# Amplifiers.net
KiCad netlist of a schematic drawn in Altium Designer
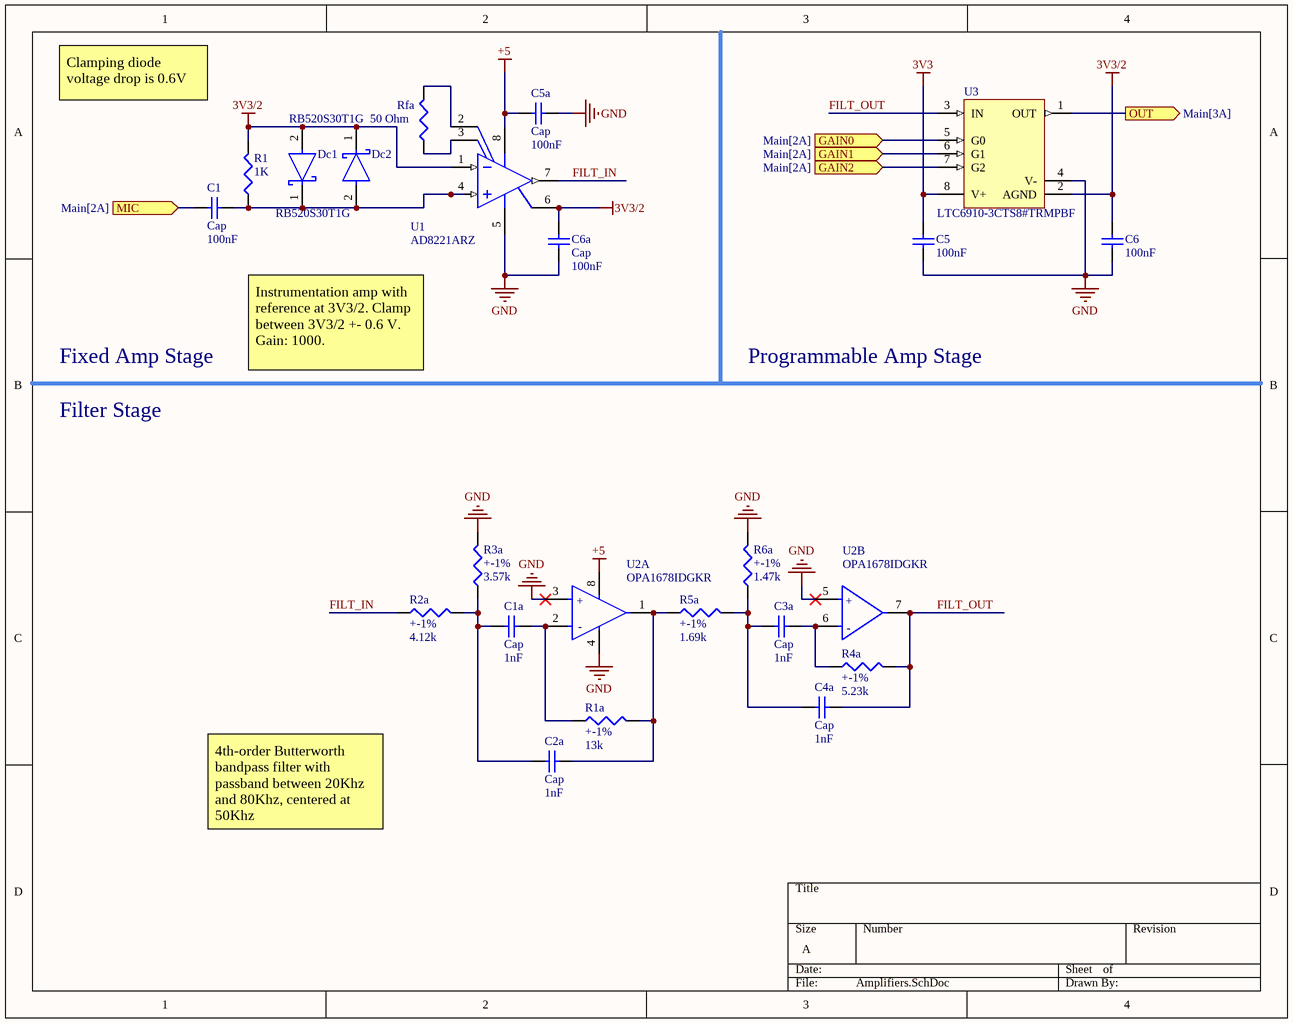
[diagram p0: Amplifiers.SchDoc]

(export (version "E")
  (design (tool "Eeschema 10.0.6"))
  (components
    (comp (ref "C1")
      (value "Cap")
      (footprint "C0805")
      (description "Capacitor")
      (fields (field (name "ALTIUM_VALUE") "100nF") (field (name "PUBLISHER") "Altium Limited"))
      (libsource (lib "Miscellaneous Devices") (part "Cap"))
    )
    (comp (ref "C1a")
      (value "Cap")
      (footprint "C0805")
      (description "Capacitor")
      (fields (field (name "ALTIUM_VALUE") "1nF") (field (name "PUBLISHER") "Altium Limited"))
      (libsource (lib "Miscellaneous Devices") (part "Cap"))
    )
    (comp (ref "C2a")
      (value "Cap")
      (footprint "C0805")
      (description "Capacitor")
      (fields (field (name "ALTIUM_VALUE") "1nF") (field (name "PUBLISHER") "Altium Limited"))
      (libsource (lib "Miscellaneous Devices") (part "Cap"))
    )
    (comp (ref "C3a")
      (value "Cap")
      (footprint "C0805")
      (description "Capacitor")
      (fields (field (name "ALTIUM_VALUE") "1nF") (field (name "PUBLISHER") "Altium Limited"))
      (libsource (lib "Miscellaneous Devices") (part "Cap"))
    )
    (comp (ref "C4a")
      (value "Cap")
      (footprint "C0805")
      (description "Capacitor")
      (fields (field (name "ALTIUM_VALUE") "1nF") (field (name "PUBLISHER") "Altium Limited"))
      (libsource (lib "Miscellaneous Devices") (part "Cap"))
    )
    (comp (ref "C5")
      (value "100nF")
      (footprint "C0805")
      (description "Capacitor")
      (fields (field (name "PUBLISHER") "Altium Limited"))
      (libsource (lib "Miscellaneous Devices") (part "Cap"))
    )
    (comp (ref "C5a")
      (value "Cap")
      (footprint "C0805")
      (description "Capacitor")
      (fields (field (name "ALTIUM_VALUE") "100nF") (field (name "PUBLISHER") "Altium Limited"))
      (libsource (lib "Miscellaneous Devices") (part "Cap"))
    )
    (comp (ref "C6")
      (value "100nF")
      (footprint "C0805")
      (description "Capacitor")
      (fields (field (name "PUBLISHER") "Altium Limited"))
      (libsource (lib "Miscellaneous Devices") (part "Cap"))
    )
    (comp (ref "C6a")
      (value "Cap")
      (footprint "C0805")
      (description "Capacitor")
      (fields (field (name "ALTIUM_VALUE") "100nF") (field (name "PUBLISHER") "Altium Limited"))
      (libsource (lib "Miscellaneous Devices") (part "Cap"))
    )
    (comp (ref "Dc1")
      (value "RB520S30T1G")
      (footprint "FP-502-01-MFG")
      (description "DIODE SCHOTTKY 30V 200MA SOD523")
      (libsource (lib "Altium Content Vault") (part "1d6ec82d83fb6aee721767c19dac4b9"))
    )
    (comp (ref "Dc2")
      (value "RB520S30T1G")
      (footprint "FP-502-01-MFG")
      (description "DIODE SCHOTTKY 30V 200MA SOD523")
      (libsource (lib "Altium Content Vault") (part "1d6ec82d83fb6aee721767c19dac4b9"))
    )
    (comp (ref "R1")
      (value "1K")
      (footprint "J1-0603")
      (description "Resistor")
      (fields (field (name "PUBLISHER") "Altium Limited"))
      (libsource (lib "Miscellaneous Devices") (part "Res3"))
    )
    (comp (ref "R1a")
      (value "+-1%")
      (footprint "J1-0603")
      (description "Resistor")
      (fields (field (name "ALTIUM_VALUE") "13k") (field (name "PUBLISHER") "Altium Limited"))
      (libsource (lib "Miscellaneous Devices") (part "Res3"))
    )
    (comp (ref "R2a")
      (value "+-1%")
      (footprint "J1-0603")
      (description "Resistor")
      (fields (field (name "ALTIUM_VALUE") "4.12k") (field (name "PUBLISHER") "Altium Limited"))
      (libsource (lib "Miscellaneous Devices") (part "Res3"))
    )
    (comp (ref "R3a")
      (value "+-1%")
      (footprint "J1-0603")
      (description "Resistor")
      (fields (field (name "ALTIUM_VALUE") "3.57k") (field (name "PUBLISHER") "Altium Limited"))
      (libsource (lib "Miscellaneous Devices") (part "Res3"))
    )
    (comp (ref "R4a")
      (value "+-1%")
      (footprint "J1-0603")
      (description "Resistor")
      (fields (field (name "ALTIUM_VALUE") "5.23k") (field (name "PUBLISHER") "Altium Limited"))
      (libsource (lib "Miscellaneous Devices") (part "Res3"))
    )
    (comp (ref "R5a")
      (value "+-1%")
      (footprint "J1-0603")
      (description "Resistor")
      (fields (field (name "ALTIUM_VALUE") "1.69k") (field (name "PUBLISHER") "Altium Limited"))
      (libsource (lib "Miscellaneous Devices") (part "Res3"))
    )
    (comp (ref "R6a")
      (value "+-1%")
      (footprint "J1-0603")
      (description "Resistor")
      (fields (field (name "ALTIUM_VALUE") "1.47k") (field (name "PUBLISHER") "Altium Limited"))
      (libsource (lib "Miscellaneous Devices") (part "Res3"))
    )
    (comp (ref "Rfa")
      (value "50 Ohm")
      (footprint "J1-0603")
      (description "Resistor")
      (fields (field (name "PUBLISHER") "Altium Limited"))
      (libsource (lib "Miscellaneous Devices") (part "Res3"))
    )
    (comp (ref "U1")
      (value "AD8221ARZ")
      (footprint "ADI-R-8_M")
      (description "Precision Instrumentation Amplifier, 2 V/us, -40 to 125 degC, 8-Pin SOIC (R-8), RoHS, Tube")
      (fields (field (name "MANUFACTURER") "Analog Devices"))
      (libsource (lib "Altium Content Vault") (part "ADI-AD8221-8"))
    )
    (comp (ref "U2")
      (value "OPA1678IDGKR")
      (footprint "FP-DGK0008A-IPC_C")
      (description "IC AUDIO 2 CIRCUIT 8VSSOP")
      (libsource (lib "Altium Content Vault") (part "499df5fc91ff7ad023bcaf249d8becd"))
    )
    (comp (ref "U3")
      (value "LTC6910-3CTS8#TRMPBF")
      (footprint "LT-TS8-8-TSOT-23_V")
      (fields
        (field (name "LINEAR TECHNOLOGY PART NUMBER") "LTC6910-3")
        (field (name "MANUFACTURER") "Linear Technology")
      )
      (libsource (lib "Altium Content Vault") (part "LT-LTC6910-TS8-8"))
    )
  )
  (nets
    (net (code "1") (name "+5") (class "Default")
      (node (ref "C5a") (pin "1") (pinfunction "1_1") (pintype "passive"))
      (node (ref "U1") (pin "8") (pinfunction "VS+_8") (pintype "power_in"))
      (node (ref "U2") (pin "8") (pinfunction "V+_8") (pintype "power_in"))
    )
    (net (code "2") (name "/FILT_IN") (class "Default")
      (node (ref "R2a") (pin "1") (pinfunction "1_1") (pintype "passive"))
      (node (ref "U1") (pin "7") (pinfunction "VOUT_7") (pintype "output"))
    )
    (net (code "3") (name "/FILT_OUT") (class "Default")
      (node (ref "C4a") (pin "2") (pinfunction "2_2") (pintype "passive"))
      (node (ref "R4a") (pin "2") (pinfunction "2_2") (pintype "passive"))
      (node (ref "U2") (pin "7") (pinfunction "OUT_B_7") (pintype "passive"))
      (node (ref "U3") (pin "3") (pinfunction "IN_3") (pintype "input"))
    )
    (net (code "4") (name "/GAIN0") (class "Default")
      (node (ref "U3") (pin "5") (pinfunction "G0_5") (pintype "input"))
    )
    (net (code "5") (name "/GAIN1") (class "Default")
      (node (ref "U3") (pin "6") (pinfunction "G1_6") (pintype "input"))
    )
    (net (code "6") (name "/GAIN2") (class "Default")
      (node (ref "U3") (pin "7") (pinfunction "G2_7") (pintype "input"))
    )
    (net (code "7") (name "/MIC") (class "Default")
      (node (ref "C1") (pin "1") (pinfunction "1_1") (pintype "passive"))
    )
    (net (code "8") (name "/OUT") (class "Default")
      (node (ref "U3") (pin "1") (pinfunction "OUT_1") (pintype "output"))
    )
    (net (code "9") (name "3V3") (class "Default")
      (node (ref "C5") (pin "2") (pinfunction "2_2") (pintype "passive"))
      (node (ref "U3") (pin "8") (pinfunction "V+_8") (pintype "power_in"))
    )
    (net (code "10") (name "3V3{slash}2") (class "Default")
      (node (ref "C6") (pin "2") (pinfunction "2_2") (pintype "passive"))
      (node (ref "C6a") (pin "2") (pinfunction "2_2") (pintype "passive"))
      (node (ref "Dc1") (pin "2") (pinfunction "A_2") (pintype "passive"))
      (node (ref "Dc2") (pin "1") (pinfunction "C_1") (pintype "passive"))
      (node (ref "R1") (pin "2") (pinfunction "2_2") (pintype "passive"))
      (node (ref "U1") (pin "1") (pinfunction "IN-_1") (pintype "input"))
      (node (ref "U1") (pin "6") (pinfunction "REF_6") (pintype "passive"))
      (node (ref "U3") (pin "2") (pinfunction "AGND_2") (pintype "power_in"))
    )
    (net (code "11") (name "GND") (class "Default")
      (node (ref "C5") (pin "1") (pinfunction "1_1") (pintype "passive"))
      (node (ref "C5a") (pin "2") (pinfunction "2_2") (pintype "passive"))
      (node (ref "C6") (pin "1") (pinfunction "1_1") (pintype "passive"))
      (node (ref "C6a") (pin "1") (pinfunction "1_1") (pintype "passive"))
      (node (ref "R3a") (pin "2") (pinfunction "2_2") (pintype "passive"))
      (node (ref "R6a") (pin "2") (pinfunction "2_2") (pintype "passive"))
      (node (ref "U1") (pin "5") (pinfunction "VS-_5") (pintype "power_in"))
      (node (ref "U2") (pin "3") (pinfunction "+IN_A_3") (pintype "tri_state"))
      (node (ref "U2") (pin "4") (pinfunction "V-_4") (pintype "power_in"))
      (node (ref "U2") (pin "5") (pinfunction "+IN_B_5") (pintype "tri_state"))
      (node (ref "U3") (pin "4") (pinfunction "V-_4") (pintype "power_in"))
    )
    (net (code "12") (name "Net-(C1a-Pad1)") (class "Default")
      (node (ref "C1a") (pin "1") (pinfunction "1_1") (pintype "passive"))
      (node (ref "C2a") (pin "1") (pinfunction "1_1") (pintype "passive"))
      (node (ref "R2a") (pin "2") (pinfunction "2_2") (pintype "passive"))
      (node (ref "R3a") (pin "1") (pinfunction "1_1") (pintype "passive"))
    )
    (net (code "13") (name "Net-(C3a-Pad1)") (class "Default")
      (node (ref "C3a") (pin "1") (pinfunction "1_1") (pintype "passive"))
      (node (ref "C4a") (pin "1") (pinfunction "1_1") (pintype "passive"))
      (node (ref "R5a") (pin "2") (pinfunction "2_2") (pintype "passive"))
      (node (ref "R6a") (pin "1") (pinfunction "1_1") (pintype "passive"))
    )
    (net (code "14") (name "Net-(Dc1-C)") (class "Default")
      (node (ref "C1") (pin "2") (pinfunction "2_2") (pintype "passive"))
      (node (ref "Dc1") (pin "1") (pinfunction "C_1") (pintype "passive"))
      (node (ref "Dc2") (pin "2") (pinfunction "A_2") (pintype "passive"))
      (node (ref "R1") (pin "1") (pinfunction "1_1") (pintype "passive"))
      (node (ref "U1") (pin "4") (pinfunction "IN+_4") (pintype "input"))
    )
    (net (code "15") (name "Net-(Rfa-Pad1)") (class "Default")
      (node (ref "Rfa") (pin "1") (pinfunction "1_1") (pintype "passive"))
      (node (ref "U1") (pin "3") (pinfunction "RG_3") (pintype "passive"))
    )
    (net (code "16") (name "Net-(Rfa-Pad2)") (class "Default")
      (node (ref "Rfa") (pin "2") (pinfunction "2_2") (pintype "passive"))
      (node (ref "U1") (pin "2") (pinfunction "RG_2") (pintype "passive"))
    )
    (net (code "17") (name "Net-(U2A--IN_A)") (class "Default")
      (node (ref "C1a") (pin "2") (pinfunction "2_2") (pintype "passive"))
      (node (ref "R1a") (pin "1") (pinfunction "1_1") (pintype "passive"))
      (node (ref "U2") (pin "2") (pinfunction "-IN_A_2") (pintype "tri_state"))
    )
    (net (code "18") (name "Net-(U2A-OUT_A)") (class "Default")
      (node (ref "C2a") (pin "2") (pinfunction "2_2") (pintype "passive"))
      (node (ref "R1a") (pin "2") (pinfunction "2_2") (pintype "passive"))
      (node (ref "R5a") (pin "1") (pinfunction "1_1") (pintype "passive"))
      (node (ref "U2") (pin "1") (pinfunction "OUT_A_1") (pintype "passive"))
    )
    (net (code "19") (name "Net-(U2B--IN_B)") (class "Default")
      (node (ref "C3a") (pin "2") (pinfunction "2_2") (pintype "passive"))
      (node (ref "R4a") (pin "1") (pinfunction "1_1") (pintype "passive"))
      (node (ref "U2") (pin "6") (pinfunction "-IN_B_6") (pintype "tri_state"))
    )
  )
)
